# STM32F4.net
KiCad netlist of a schematic drawn in Altium Designer
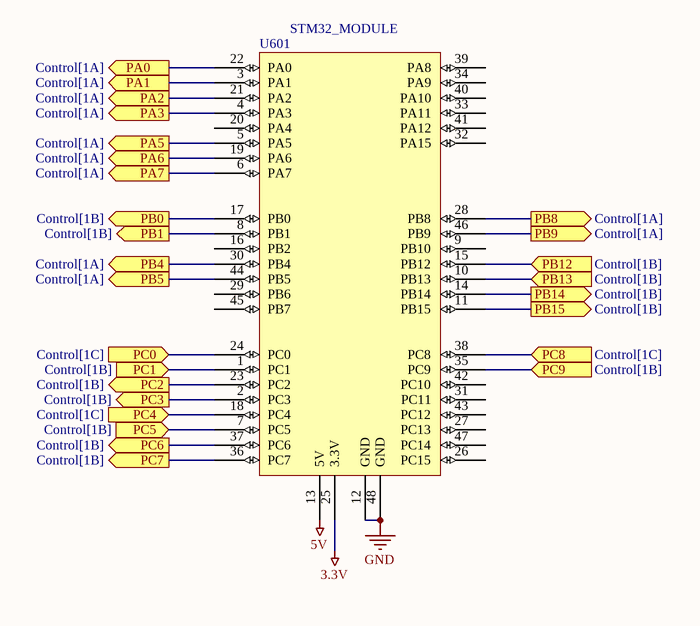
[diagram p0: STM32F4.SchDoc]

(export (version "E")
  (design (tool "Eeschema 10.0.6"))
  (components
    (comp (ref "U601")
      (value "STM32_MODULE")
      (footprint "DIP_STM32_MODULE")
      (description "processor")
      (fields (field (name "SOURCE") "robit_ic.SchLib"))
      (libsource (lib "robit circuit") (part "STM32_MODULE"))
    )
  )
  (nets
    (net (code "1") (name "/PA0") (class "Default")
      (node (ref "U601") (pin "22") (pinfunction "PA0_22") (pintype "bidirectional"))
    )
    (net (code "2") (name "/PA1") (class "Default")
      (node (ref "U601") (pin "3") (pinfunction "PA1_3") (pintype "bidirectional"))
    )
    (net (code "3") (name "/PA2") (class "Default")
      (node (ref "U601") (pin "21") (pinfunction "PA2_21") (pintype "bidirectional"))
    )
    (net (code "4") (name "/PA3") (class "Default")
      (node (ref "U601") (pin "4") (pinfunction "PA3_4") (pintype "bidirectional"))
    )
    (net (code "5") (name "/PA5") (class "Default")
      (node (ref "U601") (pin "5") (pinfunction "PA5_5") (pintype "bidirectional"))
    )
    (net (code "6") (name "/PA6") (class "Default")
      (node (ref "U601") (pin "19") (pinfunction "PA6_19") (pintype "bidirectional"))
    )
    (net (code "7") (name "/PA7") (class "Default")
      (node (ref "U601") (pin "6") (pinfunction "PA7_6") (pintype "bidirectional"))
    )
    (net (code "8") (name "/PB0") (class "Default")
      (node (ref "U601") (pin "17") (pinfunction "PB0_17") (pintype "bidirectional"))
    )
    (net (code "9") (name "/PB1") (class "Default")
      (node (ref "U601") (pin "8") (pinfunction "PB1_8") (pintype "bidirectional"))
    )
    (net (code "10") (name "/PB4") (class "Default")
      (node (ref "U601") (pin "30") (pinfunction "PB4_30") (pintype "bidirectional"))
    )
    (net (code "11") (name "/PB5") (class "Default")
      (node (ref "U601") (pin "44") (pinfunction "PB5_44") (pintype "bidirectional"))
    )
    (net (code "12") (name "/PB8") (class "Default")
      (node (ref "U601") (pin "28") (pinfunction "PB8_28") (pintype "bidirectional"))
    )
    (net (code "13") (name "/PB9") (class "Default")
      (node (ref "U601") (pin "46") (pinfunction "PB9_46") (pintype "bidirectional"))
    )
    (net (code "14") (name "/PB12") (class "Default")
      (node (ref "U601") (pin "15") (pinfunction "PB12_15") (pintype "bidirectional"))
    )
    (net (code "15") (name "/PB13") (class "Default")
      (node (ref "U601") (pin "10") (pinfunction "PB13_10") (pintype "bidirectional"))
    )
    (net (code "16") (name "/PB14") (class "Default")
      (node (ref "U601") (pin "14") (pinfunction "PB14_14") (pintype "bidirectional"))
    )
    (net (code "17") (name "/PB15") (class "Default")
      (node (ref "U601") (pin "11") (pinfunction "PB15_11") (pintype "bidirectional"))
    )
    (net (code "18") (name "/PC0") (class "Default")
      (node (ref "U601") (pin "24") (pinfunction "PC0_24") (pintype "bidirectional"))
    )
    (net (code "19") (name "/PC1") (class "Default")
      (node (ref "U601") (pin "1") (pinfunction "PC1_1") (pintype "bidirectional"))
    )
    (net (code "20") (name "/PC2") (class "Default")
      (node (ref "U601") (pin "23") (pinfunction "PC2_23") (pintype "bidirectional"))
    )
    (net (code "21") (name "/PC3") (class "Default")
      (node (ref "U601") (pin "2") (pinfunction "PC3_2") (pintype "bidirectional"))
    )
    (net (code "22") (name "/PC4") (class "Default")
      (node (ref "U601") (pin "18") (pinfunction "PC4_18") (pintype "bidirectional"))
    )
    (net (code "23") (name "/PC5") (class "Default")
      (node (ref "U601") (pin "7") (pinfunction "PC5_7") (pintype "bidirectional"))
    )
    (net (code "24") (name "/PC6") (class "Default")
      (node (ref "U601") (pin "37") (pinfunction "PC6_37") (pintype "bidirectional"))
    )
    (net (code "25") (name "/PC7") (class "Default")
      (node (ref "U601") (pin "36") (pinfunction "PC7_36") (pintype "bidirectional"))
    )
    (net (code "26") (name "/PC8") (class "Default")
      (node (ref "U601") (pin "38") (pinfunction "PC8_38") (pintype "bidirectional"))
    )
    (net (code "27") (name "/PC9") (class "Default")
      (node (ref "U601") (pin "35") (pinfunction "PC9_35") (pintype "bidirectional"))
    )
    (net (code "30") (name "3.3V") (class "Default")
      (node (ref "U601") (pin "25") (pinfunction "3.3V_25") (pintype "power_in"))
    )
    (net (code "31") (name "5V") (class "Default")
      (node (ref "U601") (pin "13") (pinfunction "5V_13") (pintype "power_in"))
    )
    (net (code "32") (name "GND") (class "Default")
      (node (ref "U601") (pin "12") (pinfunction "GND_12") (pintype "power_in"))
      (node (ref "U601") (pin "48") (pinfunction "GND_48") (pintype "power_in"))
    )
    (net (code "33") (name "unconnected-(U601-PA4-Pad20)") (class "Default")
      (node (ref "U601") (pin "20") (pinfunction "PA4_20") (pintype "bidirectional"))
    )
    (net (code "34") (name "unconnected-(U601-PA8-Pad39)") (class "Default")
      (node (ref "U601") (pin "39") (pinfunction "PA8_39") (pintype "bidirectional"))
    )
    (net (code "35") (name "unconnected-(U601-PA9-Pad34)") (class "Default")
      (node (ref "U601") (pin "34") (pinfunction "PA9_34") (pintype "bidirectional"))
    )
    (net (code "36") (name "unconnected-(U601-PA10-Pad40)") (class "Default")
      (node (ref "U601") (pin "40") (pinfunction "PA10_40") (pintype "bidirectional"))
    )
    (net (code "37") (name "unconnected-(U601-PA11-Pad33)") (class "Default")
      (node (ref "U601") (pin "33") (pinfunction "PA11_33") (pintype "bidirectional"))
    )
    (net (code "38") (name "unconnected-(U601-PA12-Pad41)") (class "Default")
      (node (ref "U601") (pin "41") (pinfunction "PA12_41") (pintype "bidirectional"))
    )
    (net (code "39") (name "unconnected-(U601-PA15-Pad32)") (class "Default")
      (node (ref "U601") (pin "32") (pinfunction "PA15_32") (pintype "bidirectional"))
    )
    (net (code "40") (name "unconnected-(U601-PB2-Pad16)") (class "Default")
      (node (ref "U601") (pin "16") (pinfunction "PB2_16") (pintype "bidirectional"))
    )
    (net (code "41") (name "unconnected-(U601-PB6-Pad29)") (class "Default")
      (node (ref "U601") (pin "29") (pinfunction "PB6_29") (pintype "bidirectional"))
    )
    (net (code "42") (name "unconnected-(U601-PB7-Pad45)") (class "Default")
      (node (ref "U601") (pin "45") (pinfunction "PB7_45") (pintype "bidirectional"))
    )
    (net (code "43") (name "unconnected-(U601-PB10-Pad9)") (class "Default")
      (node (ref "U601") (pin "9") (pinfunction "PB10_9") (pintype "bidirectional"))
    )
    (net (code "44") (name "unconnected-(U601-PC10-Pad42)") (class "Default")
      (node (ref "U601") (pin "42") (pinfunction "PC10_42") (pintype "bidirectional"))
    )
    (net (code "45") (name "unconnected-(U601-PC11-Pad31)") (class "Default")
      (node (ref "U601") (pin "31") (pinfunction "PC11_31") (pintype "bidirectional"))
    )
    (net (code "46") (name "unconnected-(U601-PC12-Pad43)") (class "Default")
      (node (ref "U601") (pin "43") (pinfunction "PC12_43") (pintype "bidirectional"))
    )
    (net (code "47") (name "unconnected-(U601-PC13-Pad27)") (class "Default")
      (node (ref "U601") (pin "27") (pinfunction "PC13_27") (pintype "bidirectional"))
    )
    (net (code "48") (name "unconnected-(U601-PC14-Pad47)") (class "Default")
      (node (ref "U601") (pin "47") (pinfunction "PC14_47") (pintype "bidirectional"))
    )
    (net (code "49") (name "unconnected-(U601-PC15-Pad26)") (class "Default")
      (node (ref "U601") (pin "26") (pinfunction "PC15_26") (pintype "bidirectional"))
    )
  )
)
